# Control.net
KiCad netlist of a schematic drawn in Altium Designer
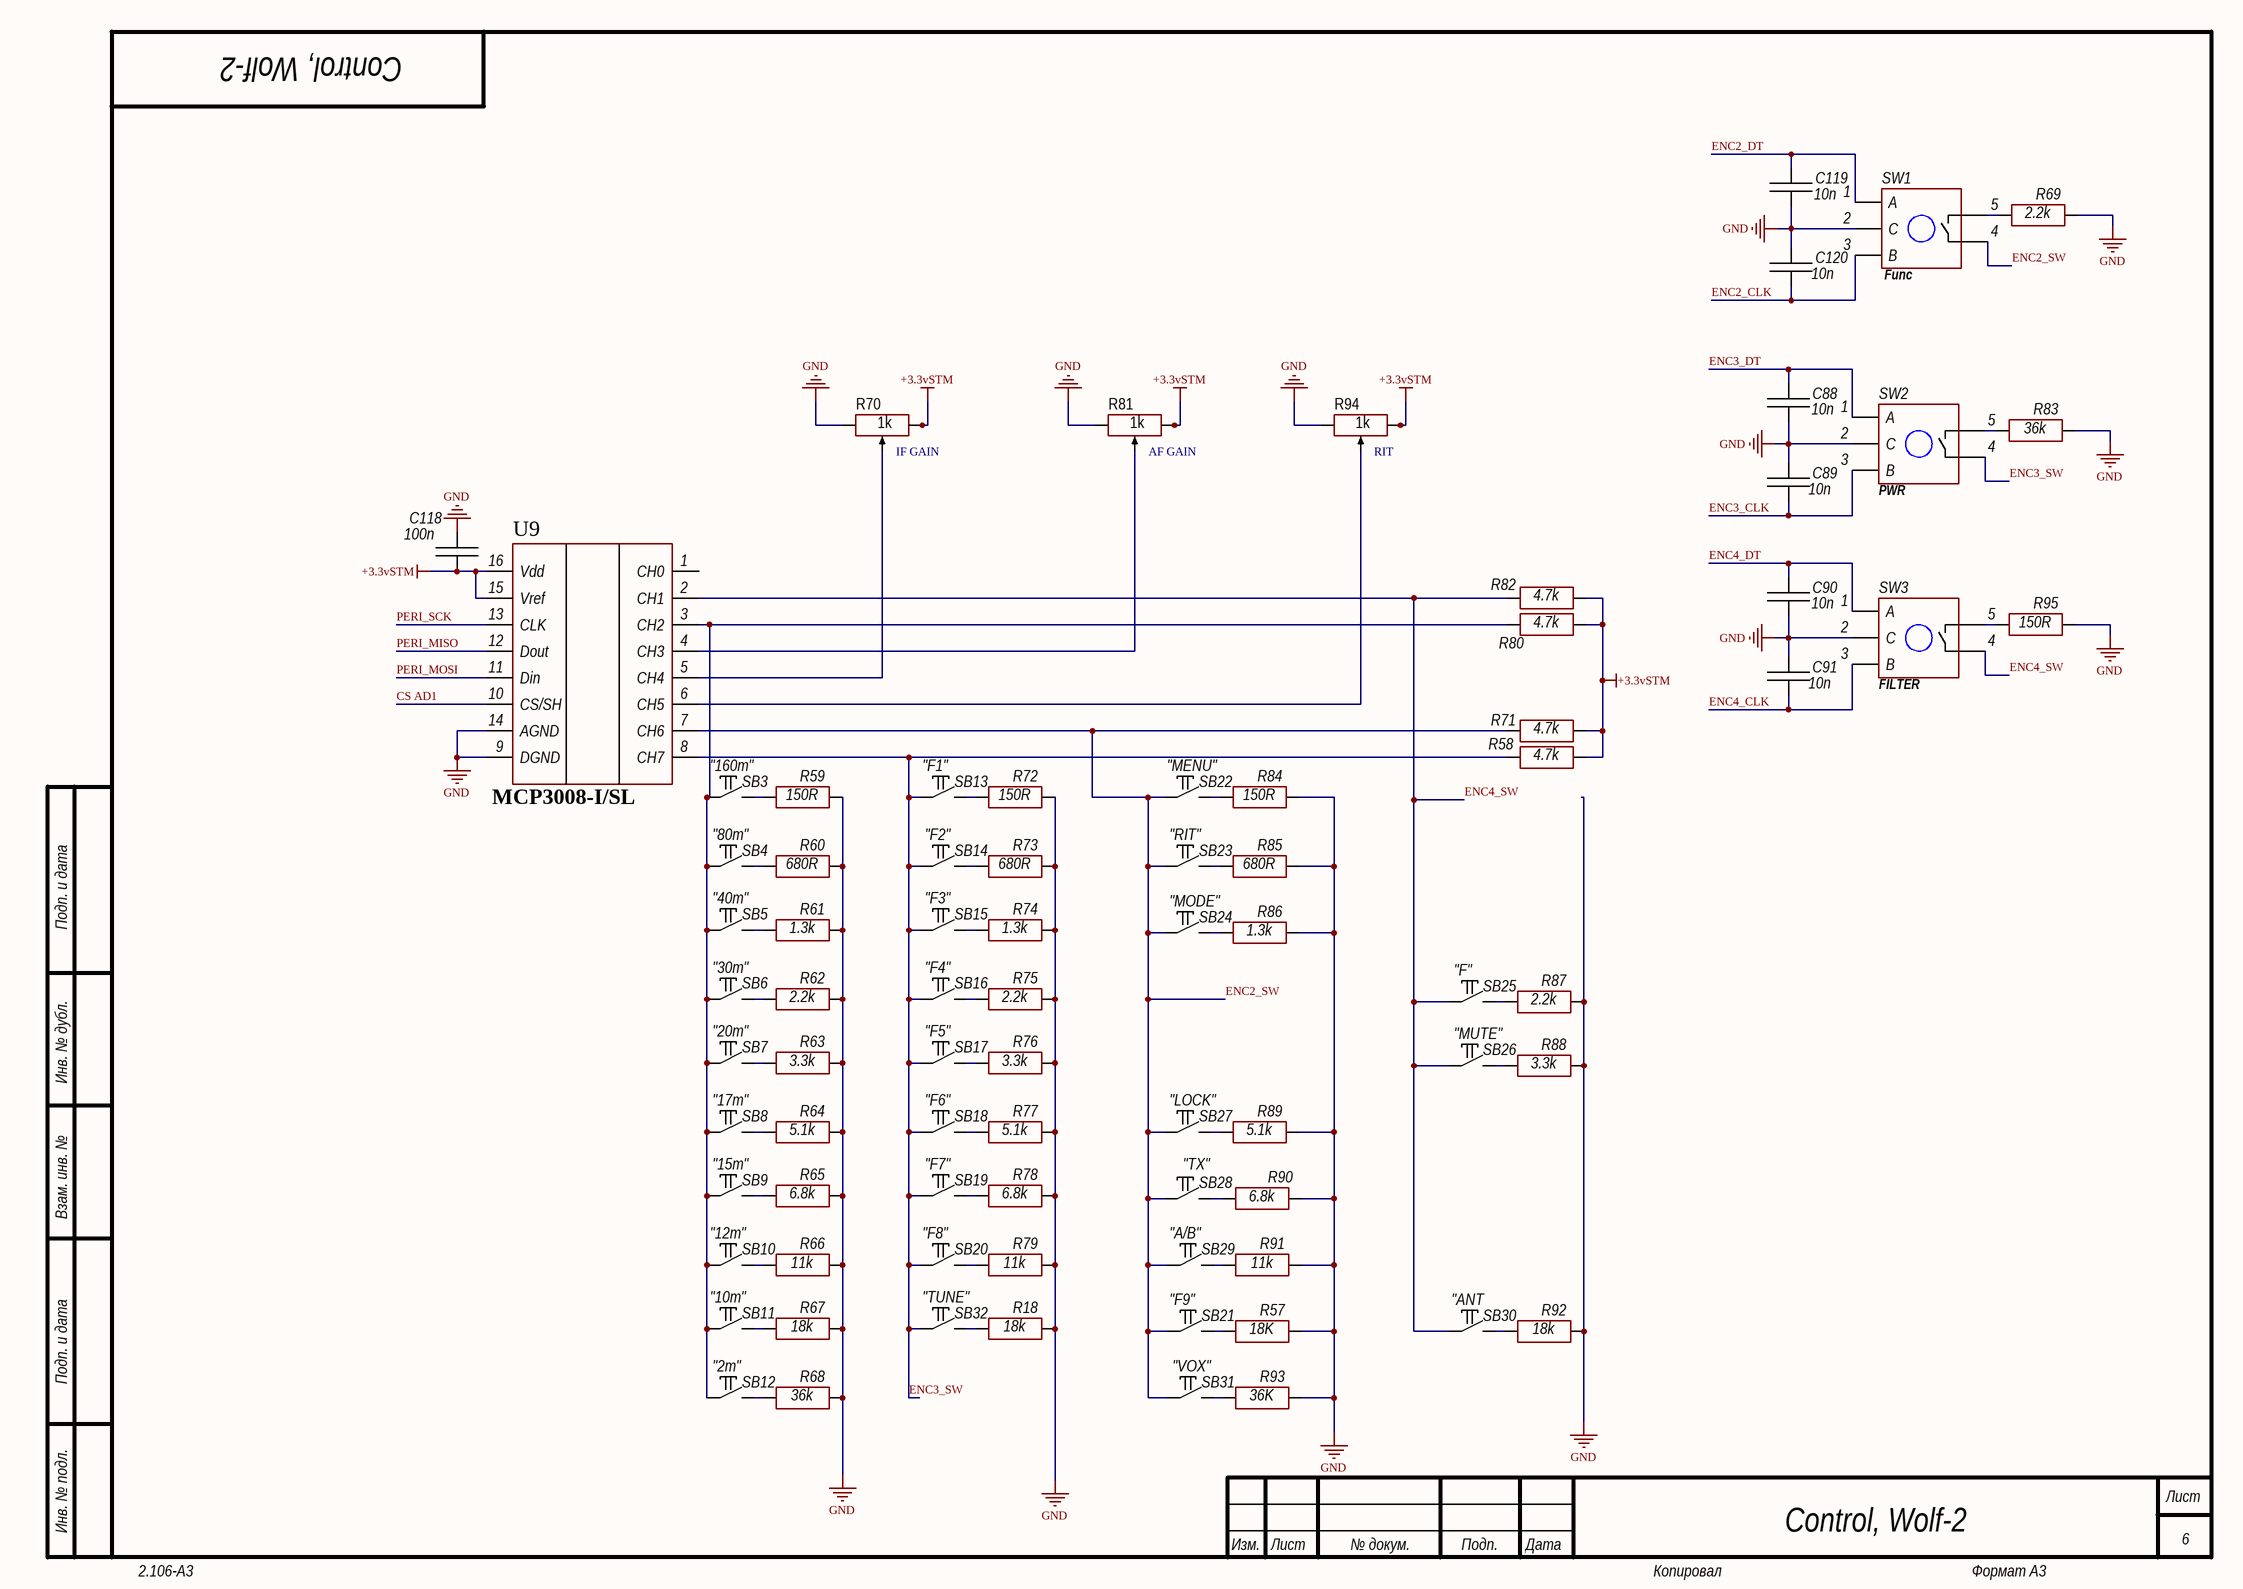
[diagram p0: Control.SchDoc]

(export (version "E")
  (design (tool "Eeschema 10.0.6"))
  (components
    (comp (ref "C88")
      (value "10n")
      (footprint "standard:CH0805C")
      (libsource (lib "Discrete") (part "Capacitor"))
    )
    (comp (ref "C89")
      (value "10n")
      (footprint "standard:CH0805C")
      (libsource (lib "Discrete") (part "Capacitor"))
    )
    (comp (ref "C90")
      (value "10n")
      (footprint "standard:CH0805C")
      (libsource (lib "Discrete") (part "Capacitor"))
    )
    (comp (ref "C91")
      (value "10n")
      (footprint "standard:CH0805C")
      (libsource (lib "Discrete") (part "Capacitor"))
    )
    (comp (ref "C118")
      (value "100n")
      (footprint "standard:CH0805C")
      (libsource (lib "Discrete") (part "Capacitor"))
    )
    (comp (ref "C119")
      (value "10n")
      (footprint "standard:CH0805C")
      (libsource (lib "Discrete") (part "Capacitor"))
    )
    (comp (ref "C120") (value "10n") (footprint "standard:CH0805C") (libsource (lib "") (part "Capacitor_1")))
    (comp (ref "R18")
      (value "18k")
      (footprint "standard:CH0805R")
      (libsource (lib "Discrete") (part "Resistor"))
    )
    (comp (ref "R57")
      (value "18K")
      (footprint "standard:CH0805R")
      (libsource (lib "Discrete") (part "Resistor"))
    )
    (comp (ref "R58")
      (value "4.7k")
      (footprint "standard:CH0805R")
      (libsource (lib "Discrete") (part "Resistor"))
    )
    (comp (ref "R59")
      (value "150R")
      (footprint "standard:CH0805R")
      (libsource (lib "Discrete") (part "Resistor"))
    )
    (comp (ref "R60")
      (value "680R")
      (footprint "standard:CH0805R")
      (libsource (lib "Discrete") (part "Resistor"))
    )
    (comp (ref "R61")
      (value "1.3k")
      (footprint "standard:CH0805R")
      (libsource (lib "Discrete") (part "Resistor"))
    )
    (comp (ref "R62")
      (value "2.2k")
      (footprint "standard:CH0805R")
      (libsource (lib "Discrete") (part "Resistor"))
    )
    (comp (ref "R63")
      (value "3.3k")
      (footprint "standard:CH0805R")
      (libsource (lib "Discrete") (part "Resistor"))
    )
    (comp (ref "R64")
      (value "5.1k")
      (footprint "standard:CH0805R")
      (libsource (lib "Discrete") (part "Resistor"))
    )
    (comp (ref "R65")
      (value "6.8k")
      (footprint "standard:CH0805R")
      (libsource (lib "Discrete") (part "Resistor"))
    )
    (comp (ref "R66")
      (value "11k")
      (footprint "standard:CH0805R")
      (libsource (lib "Discrete") (part "Resistor"))
    )
    (comp (ref "R67")
      (value "18k")
      (footprint "standard:CH0805R")
      (libsource (lib "Discrete") (part "Resistor"))
    )
    (comp (ref "R68")
      (value "36k")
      (footprint "standard:CH0805R")
      (libsource (lib "Discrete") (part "Resistor"))
    )
    (comp (ref "R69")
      (value "2.2k")
      (footprint "standard:CH0805R")
      (libsource (lib "Discrete") (part "Resistor"))
    )
    (comp (ref "R70")
      (value "1k")
      (footprint "PTV09")
      (fields
        (field (name "MANUFACTURER") "Bourns")
        (field (name "PARTNUMBER") "3296W-1-103LF")
        (field (name "VALUEMANUFACTURERPARTNUMBER") "Resistor film, 1k, ±10%, 3296W, 0.5W, -55...+125°C")
      )
      (libsource (lib "Resistor") (part "Trimmer"))
    )
    (comp (ref "R71")
      (value "4.7k")
      (footprint "standard:CH0805R")
      (libsource (lib "Discrete") (part "Resistor"))
    )
    (comp (ref "R72")
      (value "150R")
      (footprint "standard:CH0805R")
      (libsource (lib "Discrete") (part "Resistor"))
    )
    (comp (ref "R73")
      (value "680R")
      (footprint "standard:CH0805R")
      (libsource (lib "Discrete") (part "Resistor"))
    )
    (comp (ref "R74")
      (value "1.3k")
      (footprint "standard:CH0805R")
      (libsource (lib "Discrete") (part "Resistor"))
    )
    (comp (ref "R75")
      (value "2.2k")
      (footprint "standard:CH0805R")
      (libsource (lib "Discrete") (part "Resistor"))
    )
    (comp (ref "R76")
      (value "3.3k")
      (footprint "standard:CH0805R")
      (libsource (lib "Discrete") (part "Resistor"))
    )
    (comp (ref "R77")
      (value "5.1k")
      (footprint "standard:CH0805R")
      (libsource (lib "Discrete") (part "Resistor"))
    )
    (comp (ref "R78")
      (value "6.8k")
      (footprint "standard:CH0805R")
      (libsource (lib "Discrete") (part "Resistor"))
    )
    (comp (ref "R79")
      (value "11k")
      (footprint "standard:CH0805R")
      (libsource (lib "Discrete") (part "Resistor"))
    )
    (comp (ref "R80")
      (value "4.7k")
      (footprint "standard:CH0805R")
      (libsource (lib "Discrete") (part "Resistor"))
    )
    (comp (ref "R81")
      (value "1k")
      (footprint "PTV09")
      (fields
        (field (name "MANUFACTURER") "Bourns")
        (field (name "PARTNUMBER") "3296W-1-103LF")
        (field (name "VALUEMANUFACTURERPARTNUMBER") "Resistor film, 1k, ±10%, 3296W, 0.5W, -55...+125°C")
      )
      (libsource (lib "Resistor") (part "Trimmer"))
    )
    (comp (ref "R82")
      (value "4.7k")
      (footprint "standard:CH0805R")
      (libsource (lib "Discrete") (part "Resistor"))
    )
    (comp (ref "R83")
      (value "36k")
      (footprint "standard:CH0805R")
      (libsource (lib "Discrete") (part "Resistor"))
    )
    (comp (ref "R84")
      (value "150R")
      (footprint "standard:CH0805R")
      (libsource (lib "Discrete") (part "Resistor"))
    )
    (comp (ref "R85")
      (value "680R")
      (footprint "standard:CH0805R")
      (libsource (lib "Discrete") (part "Resistor"))
    )
    (comp (ref "R86")
      (value "1.3k")
      (footprint "standard:CH0805R")
      (libsource (lib "Discrete") (part "Resistor"))
    )
    (comp (ref "R87")
      (value "2.2k")
      (footprint "standard:CH0805R")
      (libsource (lib "Discrete") (part "Resistor"))
    )
    (comp (ref "R88")
      (value "3.3k")
      (footprint "standard:CH0805R")
      (libsource (lib "Discrete") (part "Resistor"))
    )
    (comp (ref "R89")
      (value "5.1k")
      (footprint "standard:CH0805R")
      (libsource (lib "Discrete") (part "Resistor"))
    )
    (comp (ref "R90")
      (value "6.8k")
      (footprint "standard:CH0805R")
      (libsource (lib "Discrete") (part "Resistor"))
    )
    (comp (ref "R91")
      (value "11k")
      (footprint "standard:CH0805R")
      (libsource (lib "Discrete") (part "Resistor"))
    )
    (comp (ref "R92")
      (value "18k")
      (footprint "standard:CH0805R")
      (libsource (lib "Discrete") (part "Resistor"))
    )
    (comp (ref "R93")
      (value "36K")
      (footprint "standard:CH0805R")
      (libsource (lib "Discrete") (part "Resistor"))
    )
    (comp (ref "R94")
      (value "1k")
      (footprint "PTV09")
      (fields
        (field (name "MANUFACTURER") "Bourns")
        (field (name "PARTNUMBER") "3296W-1-103LF")
        (field (name "VALUEMANUFACTURERPARTNUMBER") "Resistor film, 1k, ±10%, 3296W, 0.5W, -55...+125°C")
      )
      (libsource (lib "") (part "Trimmer_1"))
    )
    (comp (ref "R95")
      (value "150R")
      (footprint "standard:CH0805R")
      (libsource (lib "Discrete") (part "Resistor"))
    )
    (comp (ref "SB3")
      (value "\"160m\"")
      (footprint "custom:BUT: 6x6")
      (description "6x6 mm")
      (libsource (lib "Connectors") (part "Tactile switches"))
    )
    (comp (ref "SB4")
      (value "\"80m\"")
      (footprint "custom:BUT: 6x6")
      (description "6x6 mm")
      (libsource (lib "Connectors") (part "Tactile switches"))
    )
    (comp (ref "SB5")
      (value "\"40m\"")
      (footprint "custom:BUT: 6x6")
      (description "6x6 mm")
      (libsource (lib "Connectors") (part "Tactile switches"))
    )
    (comp (ref "SB6")
      (value "\"30m\"")
      (footprint "custom:BUT: 6x6")
      (description "6x6 mm")
      (libsource (lib "Connectors") (part "Tactile switches"))
    )
    (comp (ref "SB7")
      (value "\"20m\"")
      (footprint "custom:BUT: 6x6")
      (description "6x6 mm")
      (libsource (lib "Connectors") (part "Tactile switches"))
    )
    (comp (ref "SB8")
      (value "\"17m\"")
      (footprint "custom:BUT: 6x6")
      (description "6x6 mm")
      (libsource (lib "Connectors") (part "Tactile switches"))
    )
    (comp (ref "SB9")
      (value "\"15m\"")
      (footprint "custom:BUT: 6x6")
      (description "6x6 mm")
      (libsource (lib "Connectors") (part "Tactile switches"))
    )
    (comp (ref "SB10")
      (value "\"12m\"")
      (footprint "custom:BUT: 6x6")
      (description "6x6 mm")
      (libsource (lib "Connectors") (part "Tactile switches"))
    )
    (comp (ref "SB11")
      (value "\"10m\"")
      (footprint "custom:BUT: 6x6")
      (description "6x6 mm")
      (libsource (lib "Connectors") (part "Tactile switches"))
    )
    (comp (ref "SB12")
      (value "\"2m\"")
      (footprint "custom:BUT: 6x6")
      (description "6x6 mm")
      (libsource (lib "Connectors") (part "Tactile switches"))
    )
    (comp (ref "SB13")
      (value "\"F1\"")
      (footprint "custom:BUT: 6x6")
      (description "6x6 mm")
      (libsource (lib "Connectors") (part "Tactile switches"))
    )
    (comp (ref "SB14")
      (value "\"F2\"")
      (footprint "custom:BUT: 6x6")
      (description "6x6 mm")
      (libsource (lib "Connectors") (part "Tactile switches"))
    )
    (comp (ref "SB15")
      (value "\"F3\"")
      (footprint "custom:BUT: 6x6")
      (description "6x6 mm")
      (libsource (lib "Connectors") (part "Tactile switches"))
    )
    (comp (ref "SB16")
      (value "\"F4\"")
      (footprint "custom:BUT: 6x6")
      (description "6x6 mm")
      (libsource (lib "Connectors") (part "Tactile switches"))
    )
    (comp (ref "SB17")
      (value "\"F5\"")
      (footprint "custom:BUT: 6x6")
      (description "6x6 mm")
      (libsource (lib "Connectors") (part "Tactile switches"))
    )
    (comp (ref "SB18")
      (value "\"F6\"")
      (footprint "custom:BUT: 6x6")
      (description "6x6 mm")
      (libsource (lib "Connectors") (part "Tactile switches"))
    )
    (comp (ref "SB19")
      (value "\"F7\"")
      (footprint "custom:BUT: 6x6")
      (description "6x6 mm")
      (libsource (lib "Connectors") (part "Tactile switches"))
    )
    (comp (ref "SB20")
      (value "\"F8\"")
      (footprint "custom:BUT: 6x6")
      (description "6x6 mm")
      (libsource (lib "Connectors") (part "Tactile switches"))
    )
    (comp (ref "SB21")
      (value "\"F9\"")
      (footprint "custom:BUT: 6x6")
      (description "6x6 mm")
      (libsource (lib "Connectors") (part "Tactile switches"))
    )
    (comp (ref "SB22")
      (value "\"MENU\"")
      (footprint "custom:BUT: 6x6")
      (description "6x6 mm")
      (libsource (lib "Connectors") (part "Tactile switches"))
    )
    (comp (ref "SB23")
      (value "\"RIT\"")
      (footprint "custom:BUT: 6x6")
      (description "6x6 mm")
      (libsource (lib "Connectors") (part "Tactile switches"))
    )
    (comp (ref "SB24")
      (value "\"MODE\"")
      (footprint "custom:BUT: 6x6")
      (description "6x6 mm")
      (libsource (lib "Connectors") (part "Tactile switches"))
    )
    (comp (ref "SB25")
      (value "\"F\"")
      (footprint "custom:BUT: 6x6")
      (description "6x6 mm")
      (libsource (lib "Connectors") (part "Tactile switches"))
    )
    (comp (ref "SB26")
      (value "\"MUTE\"")
      (footprint "custom:BUT: 6x6")
      (description "6x6 mm")
      (libsource (lib "Connectors") (part "Tactile switches"))
    )
    (comp (ref "SB27")
      (value "\"LOCK\"")
      (footprint "custom:BUT: 6x6")
      (description "6x6 mm")
      (libsource (lib "Connectors") (part "Tactile switches"))
    )
    (comp (ref "SB28")
      (value "\"TX\"")
      (footprint "custom:BUT: 6x6")
      (description "6x6 mm")
      (libsource (lib "Connectors") (part "Tactile switches"))
    )
    (comp (ref "SB29")
      (value "\"A/B\"")
      (footprint "custom:BUT: 6x6")
      (description "6x6 mm")
      (libsource (lib "Connectors") (part "Tactile switches"))
    )
    (comp (ref "SB30")
      (value "\"ANT")
      (footprint "custom:BUT: 6x6")
      (description "6x6 mm")
      (libsource (lib "Connectors") (part "Tactile switches"))
    )
    (comp (ref "SB31")
      (value "\"VOX\"")
      (footprint "custom:BUT: 6x6")
      (description "6x6 mm")
      (libsource (lib "Connectors") (part "Tactile switches"))
    )
    (comp (ref "SB32")
      (value "\"TUNE\"")
      (footprint "custom:BUT: 6x6")
      (description "6x6 mm")
      (libsource (lib "Connectors") (part "Tactile switches"))
    )
    (comp (ref "SW1")
      (value "Func")
      (footprint "custom:ENC: PEC-12")
      (description "Encoder")
      (libsource (lib "Connectors") (part "PEC12"))
    )
    (comp (ref "SW2")
      (value "PWR")
      (footprint "custom:ENC: PEC-12")
      (description "Encoder")
      (libsource (lib "Connectors") (part "PEC12"))
    )
    (comp (ref "SW3")
      (value "FILTER")
      (footprint "custom:ENC: PEC-12")
      (description "Encoder")
      (libsource (lib "Connectors") (part "PEC12"))
    )
    (comp (ref "U9")
      (value "MCP3008-I/SL")
      (footprint "16-SOIC")
      (libsource (lib "Digital") (part "MCP3008-I/SL"))
    )
  )
  (nets
    (net (code "1") (name "+3.3vSTM") (class "Default")
      (node (ref "C118") (pin "1") (pinfunction "1_1") (pintype "power_in"))
      (node (ref "R58") (pin "2") (pinfunction "2_2") (pintype "passive"))
      (node (ref "R70") (pin "1") (pinfunction "1_1") (pintype "passive"))
      (node (ref "R71") (pin "2") (pinfunction "2_2") (pintype "passive"))
      (node (ref "R80") (pin "2") (pinfunction "2_2") (pintype "passive"))
      (node (ref "R81") (pin "1") (pinfunction "1_1") (pintype "passive"))
      (node (ref "R82") (pin "2") (pinfunction "2_2") (pintype "passive"))
      (node (ref "R94") (pin "1") (pinfunction "1_1") (pintype "passive"))
      (node (ref "U9") (pin "15") (pinfunction "Vref_15") (pintype "passive"))
      (node (ref "U9") (pin "16") (pinfunction "Vdd_16") (pintype "passive"))
    )
    (net (code "2") (name "/CS AD1") (class "Default")
      (node (ref "U9") (pin "10") (pinfunction "CS/SH_10") (pintype "passive"))
    )
    (net (code "3") (name "/ENC2_CLK") (class "Default")
      (node (ref "C120") (pin "1") (pinfunction "1_1") (pintype "power_in"))
      (node (ref "SW1") (pin "3") (pinfunction "B_3") (pintype "passive"))
    )
    (net (code "4") (name "/ENC2_DT") (class "Default")
      (node (ref "C119") (pin "2") (pinfunction "2_2") (pintype "power_in"))
      (node (ref "SW1") (pin "1") (pinfunction "A_1") (pintype "passive"))
    )
    (net (code "5") (name "/ENC2_SW") (class "Default")
      (node (ref "R71") (pin "1") (pinfunction "1_1") (pintype "passive"))
      (node (ref "SB21") (pin "1") (pinfunction "1_1") (pintype "passive"))
      (node (ref "SB22") (pin "1") (pinfunction "1_1") (pintype "passive"))
      (node (ref "SB23") (pin "1") (pinfunction "1_1") (pintype "passive"))
      (node (ref "SB24") (pin "1") (pinfunction "1_1") (pintype "passive"))
      (node (ref "SB27") (pin "1") (pinfunction "1_1") (pintype "passive"))
      (node (ref "SB28") (pin "1") (pinfunction "1_1") (pintype "passive"))
      (node (ref "SB29") (pin "1") (pinfunction "1_1") (pintype "passive"))
      (node (ref "SB31") (pin "1") (pinfunction "1_1") (pintype "passive"))
      (node (ref "SW1") (pin "4") (pinfunction "4_4") (pintype "passive"))
      (node (ref "U9") (pin "7") (pinfunction "CH6_7") (pintype "passive"))
    )
    (net (code "6") (name "/ENC3_CLK") (class "Default")
      (node (ref "C89") (pin "1") (pinfunction "1_1") (pintype "power_in"))
      (node (ref "SW2") (pin "3") (pinfunction "B_3") (pintype "passive"))
    )
    (net (code "7") (name "/ENC3_DT") (class "Default")
      (node (ref "C88") (pin "2") (pinfunction "2_2") (pintype "power_in"))
      (node (ref "SW2") (pin "1") (pinfunction "A_1") (pintype "passive"))
    )
    (net (code "8") (name "/ENC3_SW") (class "Default")
      (node (ref "R58") (pin "1") (pinfunction "1_1") (pintype "passive"))
      (node (ref "SB13") (pin "1") (pinfunction "1_1") (pintype "passive"))
      (node (ref "SB14") (pin "1") (pinfunction "1_1") (pintype "passive"))
      (node (ref "SB15") (pin "1") (pinfunction "1_1") (pintype "passive"))
      (node (ref "SB16") (pin "1") (pinfunction "1_1") (pintype "passive"))
      (node (ref "SB17") (pin "1") (pinfunction "1_1") (pintype "passive"))
      (node (ref "SB18") (pin "1") (pinfunction "1_1") (pintype "passive"))
      (node (ref "SB19") (pin "1") (pinfunction "1_1") (pintype "passive"))
      (node (ref "SB20") (pin "1") (pinfunction "1_1") (pintype "passive"))
      (node (ref "SB32") (pin "1") (pinfunction "1_1") (pintype "passive"))
      (node (ref "SW2") (pin "4") (pinfunction "4_4") (pintype "passive"))
      (node (ref "U9") (pin "8") (pinfunction "CH7_8") (pintype "passive"))
    )
    (net (code "9") (name "/ENC4_CLK") (class "Default")
      (node (ref "C91") (pin "1") (pinfunction "1_1") (pintype "power_in"))
      (node (ref "SW3") (pin "3") (pinfunction "B_3") (pintype "passive"))
    )
    (net (code "10") (name "/ENC4_DT") (class "Default")
      (node (ref "C90") (pin "2") (pinfunction "2_2") (pintype "power_in"))
      (node (ref "SW3") (pin "1") (pinfunction "A_1") (pintype "passive"))
    )
    (net (code "11") (name "/ENC4_SW") (class "Default")
      (node (ref "R82") (pin "1") (pinfunction "1_1") (pintype "passive"))
      (node (ref "SB25") (pin "1") (pinfunction "1_1") (pintype "passive"))
      (node (ref "SB26") (pin "1") (pinfunction "1_1") (pintype "passive"))
      (node (ref "SB30") (pin "1") (pinfunction "1_1") (pintype "passive"))
      (node (ref "SW3") (pin "4") (pinfunction "4_4") (pintype "passive"))
      (node (ref "U9") (pin "2") (pinfunction "CH1_2") (pintype "passive"))
    )
    (net (code "12") (name "/PERI_MISO") (class "Default")
      (node (ref "U9") (pin "12") (pinfunction "Dout_12") (pintype "passive"))
    )
    (net (code "13") (name "/PERI_MOSI") (class "Default")
      (node (ref "U9") (pin "11") (pinfunction "Din_11") (pintype "passive"))
    )
    (net (code "14") (name "/PERI_SCK") (class "Default")
      (node (ref "U9") (pin "13") (pinfunction "CLK_13") (pintype "passive"))
    )
    (net (code "15") (name "GND") (class "Default")
      (node (ref "C118") (pin "2") (pinfunction "2_2") (pintype "power_in"))
      (node (ref "C119") (pin "1") (pinfunction "1_1") (pintype "power_in"))
      (node (ref "C120") (pin "2") (pinfunction "2_2") (pintype "power_in"))
      (node (ref "C88") (pin "1") (pinfunction "1_1") (pintype "power_in"))
      (node (ref "C89") (pin "2") (pinfunction "2_2") (pintype "power_in"))
      (node (ref "C90") (pin "1") (pinfunction "1_1") (pintype "power_in"))
      (node (ref "C91") (pin "2") (pinfunction "2_2") (pintype "power_in"))
      (node (ref "R18") (pin "2") (pinfunction "2_2") (pintype "passive"))
      (node (ref "R57") (pin "2") (pinfunction "2_2") (pintype "passive"))
      (node (ref "R59") (pin "2") (pinfunction "2_2") (pintype "passive"))
      (node (ref "R60") (pin "2") (pinfunction "2_2") (pintype "passive"))
      (node (ref "R61") (pin "2") (pinfunction "2_2") (pintype "passive"))
      (node (ref "R62") (pin "2") (pinfunction "2_2") (pintype "passive"))
      (node (ref "R63") (pin "2") (pinfunction "2_2") (pintype "passive"))
      (node (ref "R64") (pin "2") (pinfunction "2_2") (pintype "passive"))
      (node (ref "R65") (pin "2") (pinfunction "2_2") (pintype "passive"))
      (node (ref "R66") (pin "2") (pinfunction "2_2") (pintype "passive"))
      (node (ref "R67") (pin "2") (pinfunction "2_2") (pintype "passive"))
      (node (ref "R68") (pin "2") (pinfunction "2_2") (pintype "passive"))
      (node (ref "R69") (pin "2") (pinfunction "2_2") (pintype "passive"))
      (node (ref "R70") (pin "3") (pinfunction "3_3") (pintype "passive"))
      (node (ref "R72") (pin "2") (pinfunction "2_2") (pintype "passive"))
      (node (ref "R73") (pin "2") (pinfunction "2_2") (pintype "passive"))
      (node (ref "R74") (pin "2") (pinfunction "2_2") (pintype "passive"))
      (node (ref "R75") (pin "2") (pinfunction "2_2") (pintype "passive"))
      (node (ref "R76") (pin "2") (pinfunction "2_2") (pintype "passive"))
      (node (ref "R77") (pin "2") (pinfunction "2_2") (pintype "passive"))
      (node (ref "R78") (pin "2") (pinfunction "2_2") (pintype "passive"))
      (node (ref "R79") (pin "2") (pinfunction "2_2") (pintype "passive"))
      (node (ref "R81") (pin "3") (pinfunction "3_3") (pintype "passive"))
      (node (ref "R83") (pin "2") (pinfunction "2_2") (pintype "passive"))
      (node (ref "R84") (pin "2") (pinfunction "2_2") (pintype "passive"))
      (node (ref "R85") (pin "2") (pinfunction "2_2") (pintype "passive"))
      (node (ref "R86") (pin "2") (pinfunction "2_2") (pintype "passive"))
      (node (ref "R87") (pin "2") (pinfunction "2_2") (pintype "passive"))
      (node (ref "R88") (pin "2") (pinfunction "2_2") (pintype "passive"))
      (node (ref "R89") (pin "2") (pinfunction "2_2") (pintype "passive"))
      (node (ref "R90") (pin "2") (pinfunction "2_2") (pintype "passive"))
      (node (ref "R91") (pin "2") (pinfunction "2_2") (pintype "passive"))
      (node (ref "R92") (pin "2") (pinfunction "2_2") (pintype "passive"))
      (node (ref "R93") (pin "2") (pinfunction "2_2") (pintype "passive"))
      (node (ref "R94") (pin "3") (pinfunction "3_3") (pintype "passive"))
      (node (ref "R95") (pin "2") (pinfunction "2_2") (pintype "passive"))
      (node (ref "SW1") (pin "2") (pinfunction "C_2") (pintype "passive"))
      (node (ref "SW2") (pin "2") (pinfunction "C_2") (pintype "passive"))
      (node (ref "SW3") (pin "2") (pinfunction "C_2") (pintype "passive"))
      (node (ref "U9") (pin "14") (pinfunction "AGND_14") (pintype "passive"))
      (node (ref "U9") (pin "9") (pinfunction "DGND_9") (pintype "passive"))
    )
    (net (code "16") (name "Net-(R18-Pad1)") (class "Default")
      (node (ref "R18") (pin "1") (pinfunction "1_1") (pintype "passive"))
      (node (ref "SB32") (pin "2") (pinfunction "2_2") (pintype "passive"))
    )
    (net (code "17") (name "Net-(R57-Pad1)") (class "Default")
      (node (ref "R57") (pin "1") (pinfunction "1_1") (pintype "passive"))
      (node (ref "SB21") (pin "2") (pinfunction "2_2") (pintype "passive"))
    )
    (net (code "18") (name "Net-(R59-Pad1)") (class "Default")
      (node (ref "R59") (pin "1") (pinfunction "1_1") (pintype "passive"))
      (node (ref "SB3") (pin "2") (pinfunction "2_2") (pintype "passive"))
    )
    (net (code "19") (name "Net-(R60-Pad1)") (class "Default")
      (node (ref "R60") (pin "1") (pinfunction "1_1") (pintype "passive"))
      (node (ref "SB4") (pin "2") (pinfunction "2_2") (pintype "passive"))
    )
    (net (code "20") (name "Net-(R61-Pad1)") (class "Default")
      (node (ref "R61") (pin "1") (pinfunction "1_1") (pintype "passive"))
      (node (ref "SB5") (pin "2") (pinfunction "2_2") (pintype "passive"))
    )
    (net (code "21") (name "Net-(R62-Pad1)") (class "Default")
      (node (ref "R62") (pin "1") (pinfunction "1_1") (pintype "passive"))
      (node (ref "SB6") (pin "2") (pinfunction "2_2") (pintype "passive"))
    )
    (net (code "22") (name "Net-(R63-Pad1)") (class "Default")
      (node (ref "R63") (pin "1") (pinfunction "1_1") (pintype "passive"))
      (node (ref "SB7") (pin "2") (pinfunction "2_2") (pintype "passive"))
    )
    (net (code "23") (name "Net-(R64-Pad1)") (class "Default")
      (node (ref "R64") (pin "1") (pinfunction "1_1") (pintype "passive"))
      (node (ref "SB8") (pin "2") (pinfunction "2_2") (pintype "passive"))
    )
    (net (code "24") (name "Net-(R65-Pad1)") (class "Default")
      (node (ref "R65") (pin "1") (pinfunction "1_1") (pintype "passive"))
      (node (ref "SB9") (pin "2") (pinfunction "2_2") (pintype "passive"))
    )
    (net (code "25") (name "Net-(R66-Pad1)") (class "Default")
      (node (ref "R66") (pin "1") (pinfunction "1_1") (pintype "passive"))
      (node (ref "SB10") (pin "2") (pinfunction "2_2") (pintype "passive"))
    )
    (net (code "26") (name "Net-(R67-Pad1)") (class "Default")
      (node (ref "R67") (pin "1") (pinfunction "1_1") (pintype "passive"))
      (node (ref "SB11") (pin "2") (pinfunction "2_2") (pintype "passive"))
    )
    (net (code "27") (name "Net-(R68-Pad1)") (class "Default")
      (node (ref "R68") (pin "1") (pinfunction "1_1") (pintype "passive"))
      (node (ref "SB12") (pin "2") (pinfunction "2_2") (pintype "passive"))
    )
    (net (code "28") (name "Net-(R69-Pad1)") (class "Default")
      (node (ref "R69") (pin "1") (pinfunction "1_1") (pintype "passive"))
      (node (ref "SW1") (pin "5") (pinfunction "5_5") (pintype "passive"))
    )
    (net (code "29") (name "Net-(R72-Pad1)") (class "Default")
      (node (ref "R72") (pin "1") (pinfunction "1_1") (pintype "passive"))
      (node (ref "SB13") (pin "2") (pinfunction "2_2") (pintype "passive"))
    )
    (net (code "30") (name "Net-(R73-Pad1)") (class "Default")
      (node (ref "R73") (pin "1") (pinfunction "1_1") (pintype "passive"))
      (node (ref "SB14") (pin "2") (pinfunction "2_2") (pintype "passive"))
    )
    (net (code "31") (name "Net-(R74-Pad1)") (class "Default")
      (node (ref "R74") (pin "1") (pinfunction "1_1") (pintype "passive"))
      (node (ref "SB15") (pin "2") (pinfunction "2_2") (pintype "passive"))
    )
    (net (code "32") (name "Net-(R75-Pad1)") (class "Default")
      (node (ref "R75") (pin "1") (pinfunction "1_1") (pintype "passive"))
      (node (ref "SB16") (pin "2") (pinfunction "2_2") (pintype "passive"))
    )
    (net (code "33") (name "Net-(R76-Pad1)") (class "Default")
      (node (ref "R76") (pin "1") (pinfunction "1_1") (pintype "passive"))
      (node (ref "SB17") (pin "2") (pinfunction "2_2") (pintype "passive"))
    )
    (net (code "34") (name "Net-(R77-Pad1)") (class "Default")
      (node (ref "R77") (pin "1") (pinfunction "1_1") (pintype "passive"))
      (node (ref "SB18") (pin "2") (pinfunction "2_2") (pintype "passive"))
    )
    (net (code "35") (name "Net-(R78-Pad1)") (class "Default")
      (node (ref "R78") (pin "1") (pinfunction "1_1") (pintype "passive"))
      (node (ref "SB19") (pin "2") (pinfunction "2_2") (pintype "passive"))
    )
    (net (code "36") (name "Net-(R79-Pad1)") (class "Default")
      (node (ref "R79") (pin "1") (pinfunction "1_1") (pintype "passive"))
      (node (ref "SB20") (pin "2") (pinfunction "2_2") (pintype "passive"))
    )
    (net (code "37") (name "Net-(R83-Pad1)") (class "Default")
      (node (ref "R83") (pin "1") (pinfunction "1_1") (pintype "passive"))
      (node (ref "SW2") (pin "5") (pinfunction "5_5") (pintype "passive"))
    )
    (net (code "38") (name "Net-(R84-Pad1)") (class "Default")
      (node (ref "R84") (pin "1") (pinfunction "1_1") (pintype "passive"))
      (node (ref "SB22") (pin "2") (pinfunction "2_2") (pintype "passive"))
    )
    (net (code "39") (name "Net-(R85-Pad1)") (class "Default")
      (node (ref "R85") (pin "1") (pinfunction "1_1") (pintype "passive"))
      (node (ref "SB23") (pin "2") (pinfunction "2_2") (pintype "passive"))
    )
    (net (code "40") (name "Net-(R86-Pad1)") (class "Default")
      (node (ref "R86") (pin "1") (pinfunction "1_1") (pintype "passive"))
      (node (ref "SB24") (pin "2") (pinfunction "2_2") (pintype "passive"))
    )
    (net (code "41") (name "Net-(R87-Pad1)") (class "Default")
      (node (ref "R87") (pin "1") (pinfunction "1_1") (pintype "passive"))
      (node (ref "SB25") (pin "2") (pinfunction "2_2") (pintype "passive"))
    )
    (net (code "42") (name "Net-(R88-Pad1)") (class "Default")
      (node (ref "R88") (pin "1") (pinfunction "1_1") (pintype "passive"))
      (node (ref "SB26") (pin "2") (pinfunction "2_2") (pintype "passive"))
    )
    (net (code "43") (name "Net-(R89-Pad1)") (class "Default")
      (node (ref "R89") (pin "1") (pinfunction "1_1") (pintype "passive"))
      (node (ref "SB27") (pin "2") (pinfunction "2_2") (pintype "passive"))
    )
    (net (code "44") (name "Net-(R90-Pad1)") (class "Default")
      (node (ref "R90") (pin "1") (pinfunction "1_1") (pintype "passive"))
      (node (ref "SB28") (pin "2") (pinfunction "2_2") (pintype "passive"))
    )
    (net (code "45") (name "Net-(R91-Pad1)") (class "Default")
      (node (ref "R91") (pin "1") (pinfunction "1_1") (pintype "passive"))
      (node (ref "SB29") (pin "2") (pinfunction "2_2") (pintype "passive"))
    )
    (net (code "46") (name "Net-(R92-Pad1)") (class "Default")
      (node (ref "R92") (pin "1") (pinfunction "1_1") (pintype "passive"))
      (node (ref "SB30") (pin "2") (pinfunction "2_2") (pintype "passive"))
    )
    (net (code "47") (name "Net-(R93-Pad1)") (class "Default")
      (node (ref "R93") (pin "1") (pinfunction "1_1") (pintype "passive"))
      (node (ref "SB31") (pin "2") (pinfunction "2_2") (pintype "passive"))
    )
    (net (code "48") (name "Net-(R95-Pad1)") (class "Default")
      (node (ref "R95") (pin "1") (pinfunction "1_1") (pintype "passive"))
      (node (ref "SW3") (pin "5") (pinfunction "5_5") (pintype "passive"))
    )
    (net (code "49") (name "Net-(U9-CH2)") (class "Default")
      (node (ref "R80") (pin "1") (pinfunction "1_1") (pintype "passive"))
      (node (ref "SB10") (pin "1") (pinfunction "1_1") (pintype "passive"))
      (node (ref "SB11") (pin "1") (pinfunction "1_1") (pintype "passive"))
      (node (ref "SB12") (pin "1") (pinfunction "1_1") (pintype "passive"))
      (node (ref "SB3") (pin "1") (pinfunction "1_1") (pintype "passive"))
      (node (ref "SB4") (pin "1") (pinfunction "1_1") (pintype "passive"))
      (node (ref "SB5") (pin "1") (pinfunction "1_1") (pintype "passive"))
      (node (ref "SB6") (pin "1") (pinfunction "1_1") (pintype "passive"))
      (node (ref "SB7") (pin "1") (pinfunction "1_1") (pintype "passive"))
      (node (ref "SB8") (pin "1") (pinfunction "1_1") (pintype "passive"))
      (node (ref "SB9") (pin "1") (pinfunction "1_1") (pintype "passive"))
      (node (ref "U9") (pin "3") (pinfunction "CH2_3") (pintype "passive"))
    )
    (net (code "50") (name "Net-(U9-CH3)") (class "Default")
      (node (ref "R81") (pin "2") (pinfunction "2_2") (pintype "passive"))
      (node (ref "U9") (pin "4") (pinfunction "CH3_4") (pintype "passive"))
    )
    (net (code "51") (name "Net-(U9-CH4)") (class "Default")
      (node (ref "R70") (pin "2") (pinfunction "2_2") (pintype "passive"))
      (node (ref "U9") (pin "5") (pinfunction "CH4_5") (pintype "passive"))
    )
    (net (code "52") (name "Net-(U9-CH5)") (class "Default")
      (node (ref "R94") (pin "2") (pinfunction "2_2") (pintype "passive"))
      (node (ref "U9") (pin "6") (pinfunction "CH5_6") (pintype "passive"))
    )
    (net (code "53") (name "unconnected-(U9-CH0-Pad1)") (class "Default")
      (node (ref "U9") (pin "1") (pinfunction "CH0_1") (pintype "passive"))
    )
  )
)
